# pro2310.net
KiCad netlist of a schematic drawn in EAGLE
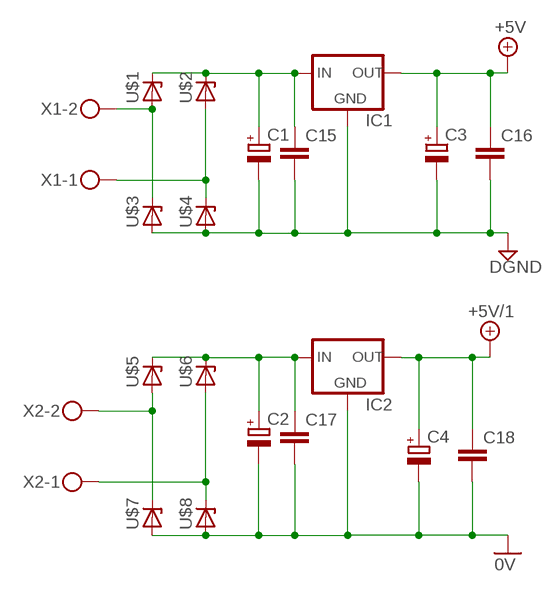
[diagram p0: schematic, sheet 1]
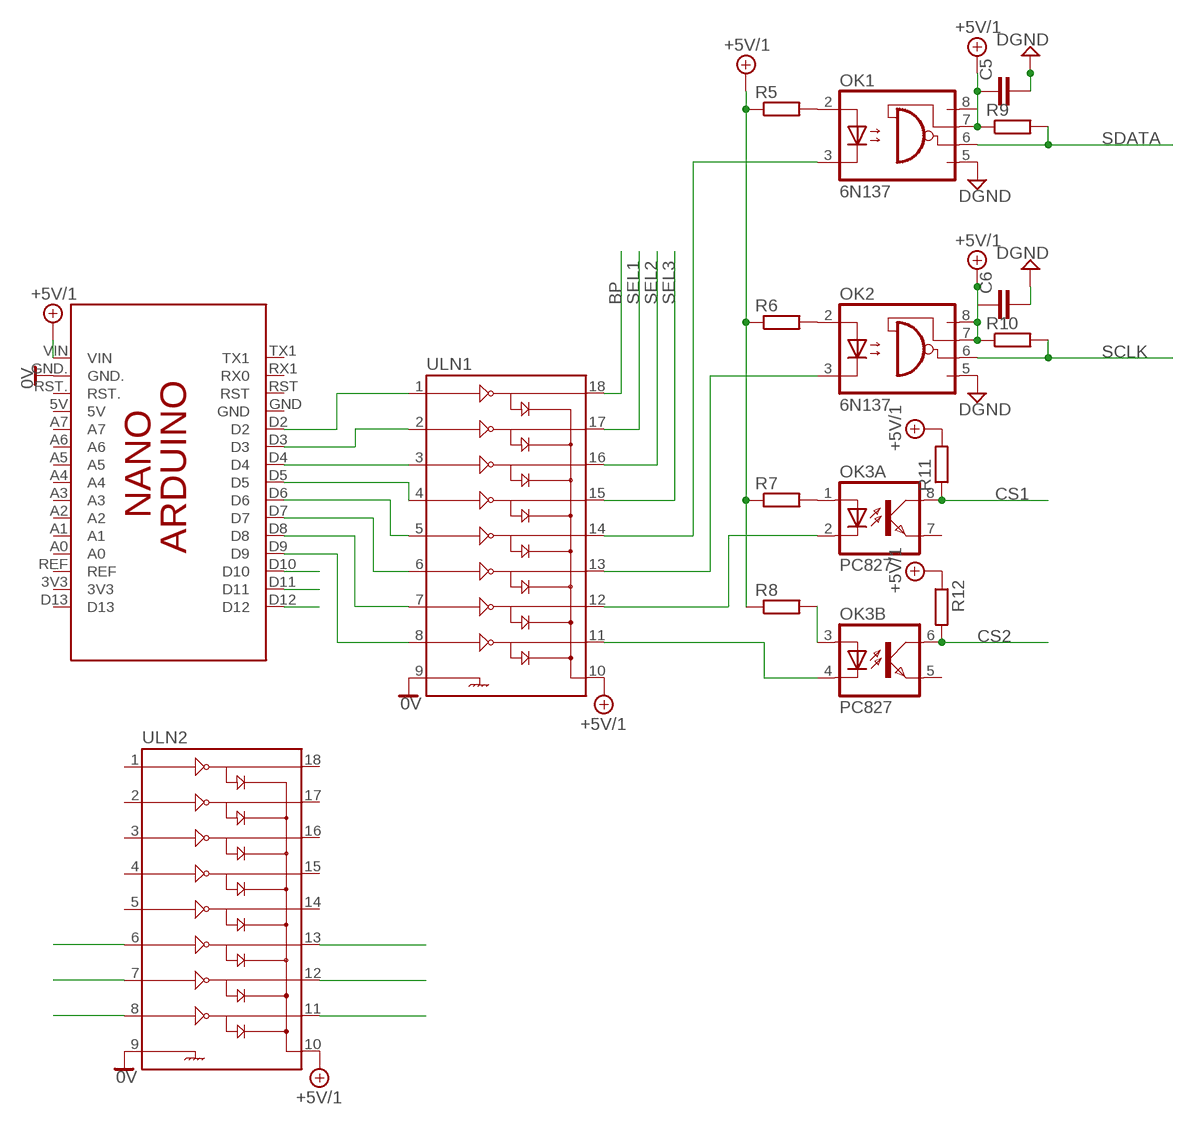
[diagram p1: schematic, sheet 2]
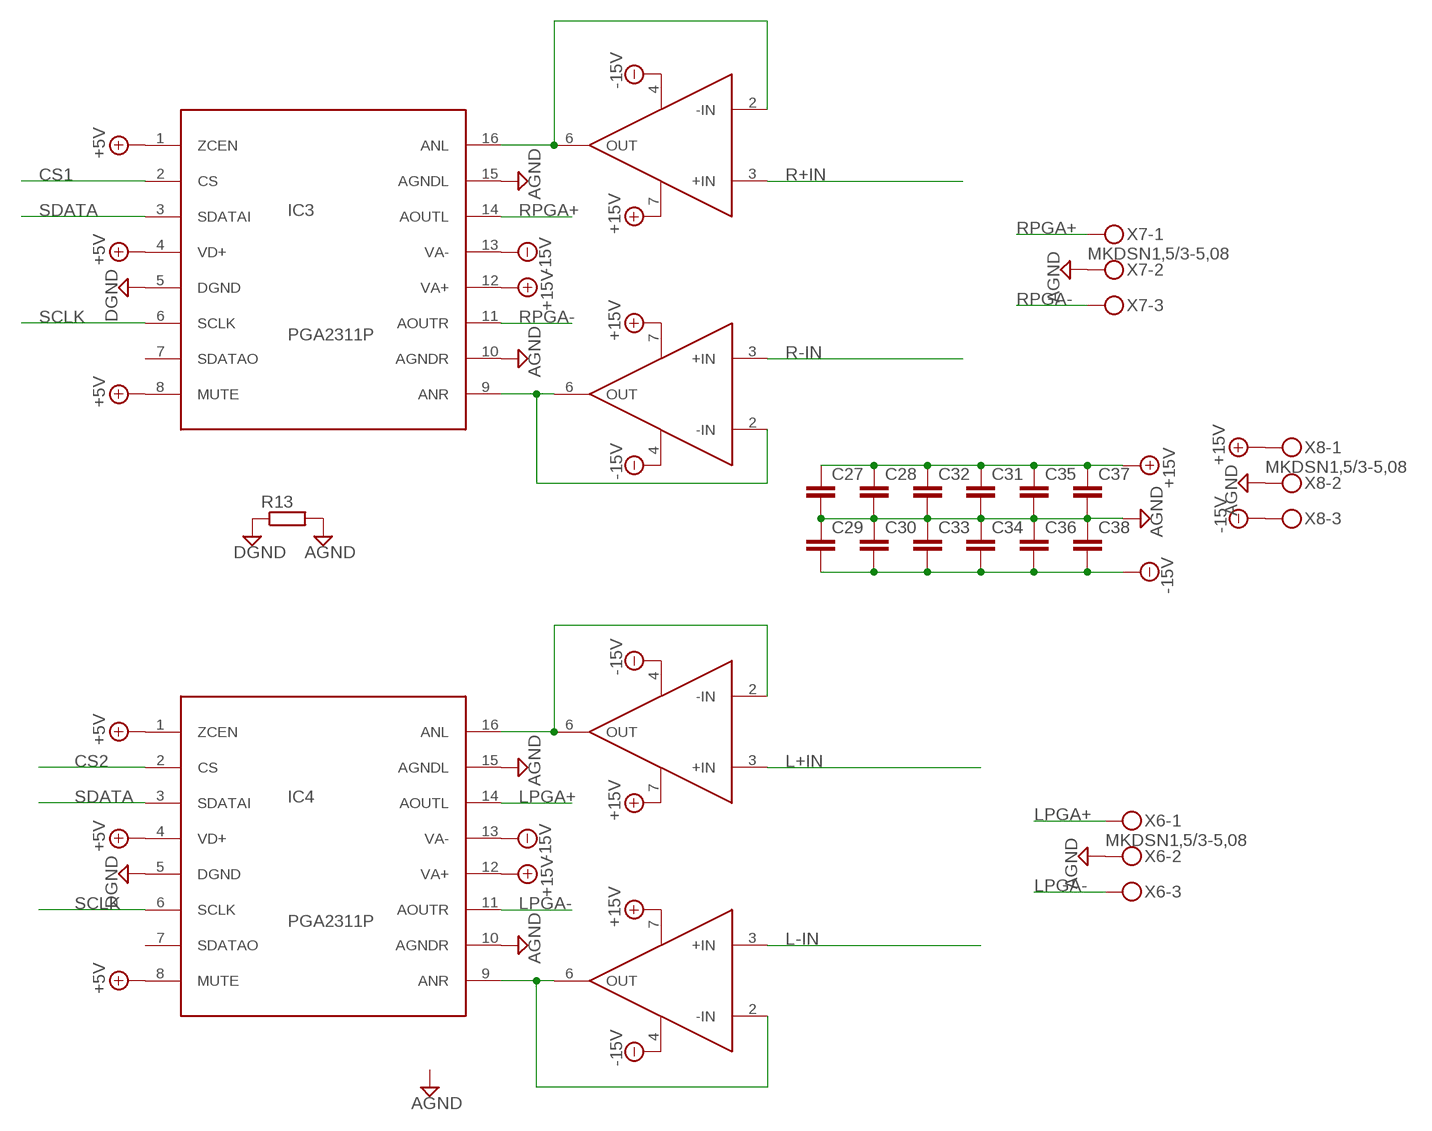
[diagram p2: schematic, sheet 3]
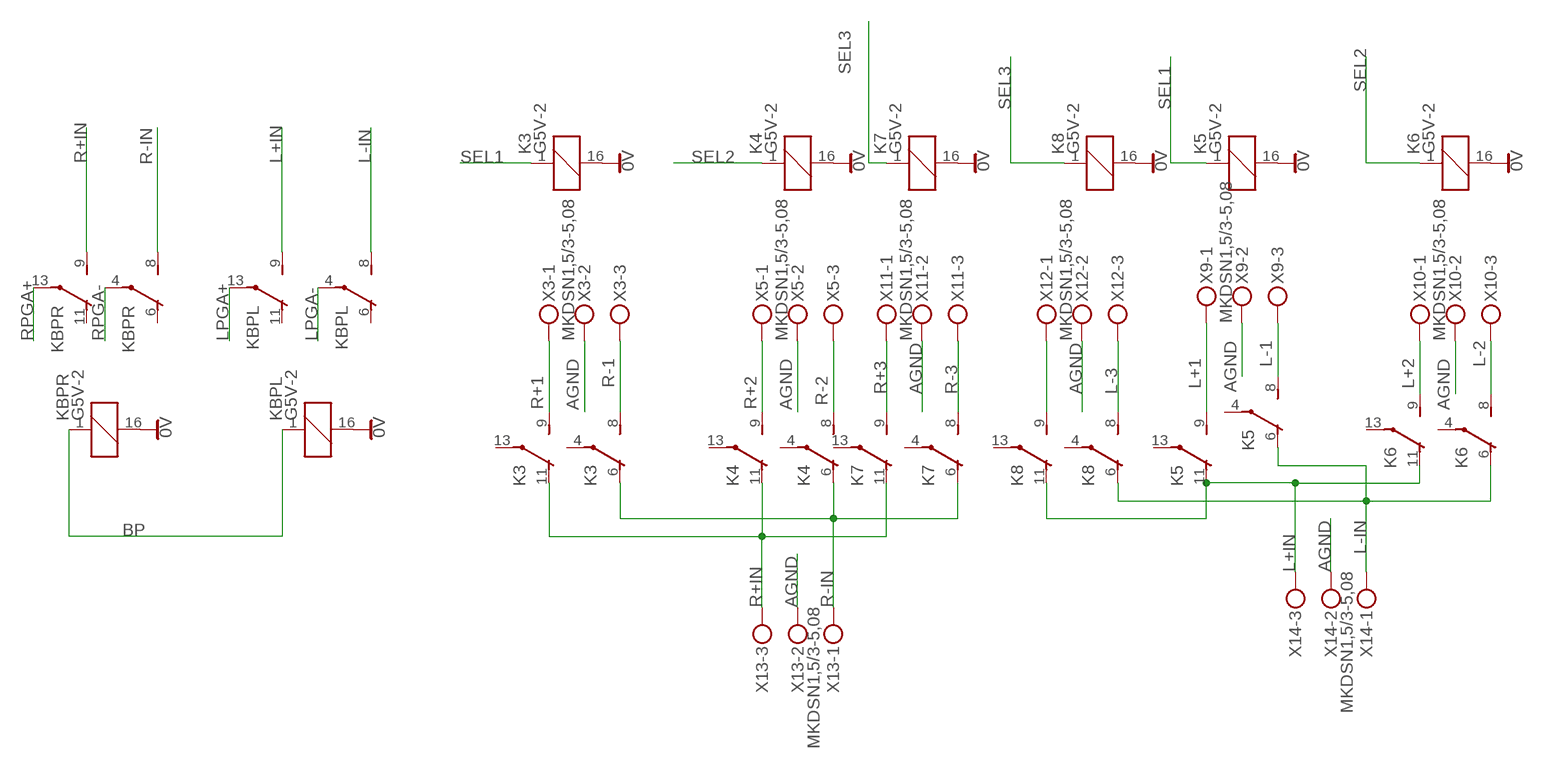
[diagram p3: schematic, sheet 4]
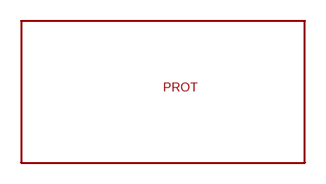
[diagram p4: schematic, sheet 5]
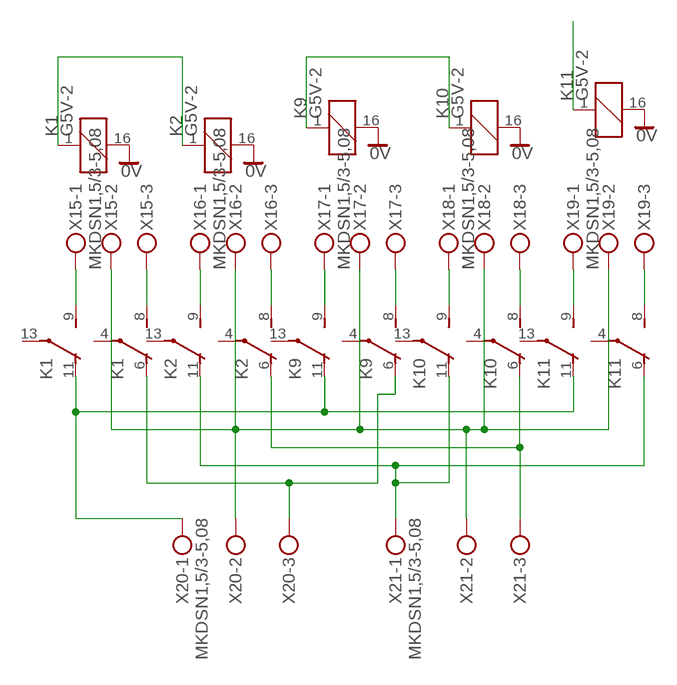
[diagram p5: schematic, sheet 6]

(export (version "E")
  (design (tool "Eeschema 10.0.6"))
  (components
    (comp (ref "C5")
      (value "C-EU025-025X050")
      (footprint "eagle-import:C025-025X050")
      (libsource (lib "eagle-import") (part "C-EU025-025X050"))
    )
    (comp (ref "C6")
      (value "C-EU025-025X050")
      (footprint "eagle-import:C025-025X050")
      (libsource (lib "eagle-import") (part "C-EU025-025X050"))
    )
    (comp (ref "OK1")
      (value "6N137")
      (footprint "eagle-import:DIL08")
      (libsource (lib "eagle-import") (part "6N137"))
    )
    (comp (ref "OK2")
      (value "6N137")
      (footprint "eagle-import:DIL08")
      (libsource (lib "eagle-import") (part "6N137"))
    )
    (comp (ref "OK3")
      (value "PC827")
      (footprint "eagle-import:DIL08")
      (libsource (lib "eagle-import") (part "PC827"))
    )
    (comp (ref "PCB1")
      (value "ARDUINO_NANO")
      (footprint "eagle-import:ARDUINO_NANO")
      (libsource (lib "eagle-import") (part "ARDUINO_NANO"))
    )
    (comp (ref "R5")
      (value "R-EU_0207/2V")
      (footprint "eagle-import:0207_2V")
      (libsource (lib "eagle-import") (part "R-EU_0207/2V"))
    )
    (comp (ref "R6")
      (value "R-EU_0207/2V")
      (footprint "eagle-import:0207_2V")
      (libsource (lib "eagle-import") (part "R-EU_0207/2V"))
    )
    (comp (ref "R7")
      (value "R-EU_0207/2V")
      (footprint "eagle-import:0207_2V")
      (libsource (lib "eagle-import") (part "R-EU_0207/2V"))
    )
    (comp (ref "R8")
      (value "R-EU_0207/2V")
      (footprint "eagle-import:0207_2V")
      (libsource (lib "eagle-import") (part "R-EU_0207/2V"))
    )
    (comp (ref "R9")
      (value "R-EU_0207/2V")
      (footprint "eagle-import:0207_2V")
      (libsource (lib "eagle-import") (part "R-EU_0207/2V"))
    )
    (comp (ref "R10")
      (value "R-EU_0207/2V")
      (footprint "eagle-import:0207_2V")
      (libsource (lib "eagle-import") (part "R-EU_0207/2V"))
    )
    (comp (ref "R11")
      (value "R-EU_0207/2V")
      (footprint "eagle-import:0207_2V")
      (libsource (lib "eagle-import") (part "R-EU_0207/2V"))
    )
    (comp (ref "R12")
      (value "R-EU_0207/2V")
      (footprint "eagle-import:0207_2V")
      (libsource (lib "eagle-import") (part "R-EU_0207/2V"))
    )
    (comp (ref "ULN1")
      (value "ULN2803DIP")
      (footprint "eagle-import:DIL18")
      (libsource (lib "eagle-import") (part "ULN2803DIP"))
    )
    (comp (ref "ULN2")
      (value "ULN2803DIP")
      (footprint "eagle-import:DIL18")
      (libsource (lib "eagle-import") (part "ULN2803DIP"))
    )
    (comp (ref "U$15")
      (value "PROT")
      (footprint "eagle-import:PROT")
      (libsource (lib "eagle-import") (part "PROT"))
    )
    (comp (ref "K1")
      (value "G5V-2")
      (footprint "eagle-import:G5V-2")
      (fields (field (name "MPN") "G5V-2 5DC"))
      (libsource (lib "eagle-import") (part "G5V-2"))
    )
    (comp (ref "K2")
      (value "G5V-2")
      (footprint "eagle-import:G5V-2")
      (fields (field (name "MPN") "G5V-2 5DC"))
      (libsource (lib "eagle-import") (part "G5V-2"))
    )
    (comp (ref "K9")
      (value "G5V-2")
      (footprint "eagle-import:G5V-2")
      (fields (field (name "MPN") "G5V-2 5DC"))
      (libsource (lib "eagle-import") (part "G5V-2"))
    )
    (comp (ref "K10")
      (value "G5V-2")
      (footprint "eagle-import:G5V-2")
      (fields (field (name "MPN") "G5V-2 5DC"))
      (libsource (lib "eagle-import") (part "G5V-2"))
    )
    (comp (ref "K11")
      (value "G5V-2")
      (footprint "eagle-import:G5V-2")
      (fields (field (name "MPN") "G5V-2 5DC"))
      (libsource (lib "eagle-import") (part "G5V-2"))
    )
    (comp (ref "X15")
      (value "MKDSN1,5/3-5,08")
      (footprint "eagle-import:MKDSN1,5_3-5,08")
      (libsource (lib "eagle-import") (part "MKDSN1,5/3-5,08"))
    )
    (comp (ref "X16")
      (value "MKDSN1,5/3-5,08")
      (footprint "eagle-import:MKDSN1,5_3-5,08")
      (libsource (lib "eagle-import") (part "MKDSN1,5/3-5,08"))
    )
    (comp (ref "X17")
      (value "MKDSN1,5/3-5,08")
      (footprint "eagle-import:MKDSN1,5_3-5,08")
      (libsource (lib "eagle-import") (part "MKDSN1,5/3-5,08"))
    )
    (comp (ref "X18")
      (value "MKDSN1,5/3-5,08")
      (footprint "eagle-import:MKDSN1,5_3-5,08")
      (libsource (lib "eagle-import") (part "MKDSN1,5/3-5,08"))
    )
    (comp (ref "X19")
      (value "MKDSN1,5/3-5,08")
      (footprint "eagle-import:MKDSN1,5_3-5,08")
      (libsource (lib "eagle-import") (part "MKDSN1,5/3-5,08"))
    )
    (comp (ref "X20")
      (value "MKDSN1,5/3-5,08")
      (footprint "eagle-import:MKDSN1,5_3-5,08")
      (libsource (lib "eagle-import") (part "MKDSN1,5/3-5,08"))
    )
    (comp (ref "X21")
      (value "MKDSN1,5/3-5,08")
      (footprint "eagle-import:MKDSN1,5_3-5,08")
      (libsource (lib "eagle-import") (part "MKDSN1,5/3-5,08"))
    )
    (comp (ref "C27")
      (value "C-EU025-025X050")
      (footprint "eagle-import:C025-025X050")
      (libsource (lib "eagle-import") (part "C-EU025-025X050"))
    )
    (comp (ref "C28")
      (value "C-EU025-025X050")
      (footprint "eagle-import:C025-025X050")
      (libsource (lib "eagle-import") (part "C-EU025-025X050"))
    )
    (comp (ref "C29")
      (value "C-EU025-025X050")
      (footprint "eagle-import:C025-025X050")
      (libsource (lib "eagle-import") (part "C-EU025-025X050"))
    )
    (comp (ref "C30")
      (value "C-EU025-025X050")
      (footprint "eagle-import:C025-025X050")
      (libsource (lib "eagle-import") (part "C-EU025-025X050"))
    )
    (comp (ref "C31")
      (value "C-EU025-025X050")
      (footprint "eagle-import:C025-025X050")
      (libsource (lib "eagle-import") (part "C-EU025-025X050"))
    )
    (comp (ref "C32")
      (value "C-EU025-025X050")
      (footprint "eagle-import:C025-025X050")
      (libsource (lib "eagle-import") (part "C-EU025-025X050"))
    )
    (comp (ref "C33")
      (value "C-EU025-025X050")
      (footprint "eagle-import:C025-025X050")
      (libsource (lib "eagle-import") (part "C-EU025-025X050"))
    )
    (comp (ref "C34")
      (value "C-EU025-025X050")
      (footprint "eagle-import:C025-025X050")
      (libsource (lib "eagle-import") (part "C-EU025-025X050"))
    )
    (comp (ref "C35")
      (value "C-EU025-025X050")
      (footprint "eagle-import:C025-025X050")
      (libsource (lib "eagle-import") (part "C-EU025-025X050"))
    )
    (comp (ref "C36")
      (value "C-EU025-025X050")
      (footprint "eagle-import:C025-025X050")
      (libsource (lib "eagle-import") (part "C-EU025-025X050"))
    )
    (comp (ref "C37")
      (value "C-EU025-025X050")
      (footprint "eagle-import:C025-025X050")
      (libsource (lib "eagle-import") (part "C-EU025-025X050"))
    )
    (comp (ref "C38")
      (value "C-EU025-025X050")
      (footprint "eagle-import:C025-025X050")
      (libsource (lib "eagle-import") (part "C-EU025-025X050"))
    )
    (comp (ref "IC3")
      (value "PGA2311P")
      (footprint "eagle-import:DIL16")
      (libsource (lib "eagle-import") (part "PGA2311P"))
    )
    (comp (ref "IC4")
      (value "PGA2311P")
      (footprint "eagle-import:DIL16")
      (libsource (lib "eagle-import") (part "PGA2311P"))
    )
    (comp (ref "R13")
      (value "R-EU_0207/7")
      (footprint "eagle-import:0207_7")
      (libsource (lib "eagle-import") (part "R-EU_0207/7"))
    )
    (comp (ref "U1")
      (value "OPA627BP")
      (footprint "eagle-import:DIL08")
      (libsource (lib "eagle-import") (part "OPA627BP"))
    )
    (comp (ref "U2")
      (value "OPA627BP")
      (footprint "eagle-import:DIL08")
      (libsource (lib "eagle-import") (part "OPA627BP"))
    )
    (comp (ref "U3")
      (value "OPA627BP")
      (footprint "eagle-import:DIL08")
      (libsource (lib "eagle-import") (part "OPA627BP"))
    )
    (comp (ref "U4")
      (value "OPA627BP")
      (footprint "eagle-import:DIL08")
      (libsource (lib "eagle-import") (part "OPA627BP"))
    )
    (comp (ref "X6")
      (value "MKDSN1,5/3-5,08")
      (footprint "eagle-import:MKDSN1,5_3-5,08")
      (libsource (lib "eagle-import") (part "MKDSN1,5/3-5,08"))
    )
    (comp (ref "X7")
      (value "MKDSN1,5/3-5,08")
      (footprint "eagle-import:MKDSN1,5_3-5,08")
      (libsource (lib "eagle-import") (part "MKDSN1,5/3-5,08"))
    )
    (comp (ref "X8")
      (value "MKDSN1,5/3-5,08")
      (footprint "eagle-import:MKDSN1,5_3-5,08")
      (libsource (lib "eagle-import") (part "MKDSN1,5/3-5,08"))
    )
    (comp (ref "C1")
      (value "CPOL-EUE5-10.5")
      (footprint "eagle-import:E5-10,5")
      (libsource (lib "eagle-import") (part "CPOL-EUE5-10.5"))
    )
    (comp (ref "C2")
      (value "CPOL-EUE5-10.5")
      (footprint "eagle-import:E5-10,5")
      (libsource (lib "eagle-import") (part "CPOL-EUE5-10.5"))
    )
    (comp (ref "C3")
      (value "CPOL-EUE3.5-8")
      (footprint "eagle-import:E3,5-8")
      (libsource (lib "eagle-import") (part "CPOL-EUE3.5-8"))
    )
    (comp (ref "C4")
      (value "CPOL-EUE3.5-8")
      (footprint "eagle-import:E3,5-8")
      (libsource (lib "eagle-import") (part "CPOL-EUE3.5-8"))
    )
    (comp (ref "C15")
      (value "C-EU050-055X075")
      (footprint "eagle-import:C050-055X075")
      (libsource (lib "eagle-import") (part "C-EU050-055X075"))
    )
    (comp (ref "C16")
      (value "C-EU050-055X075")
      (footprint "eagle-import:C050-055X075")
      (libsource (lib "eagle-import") (part "C-EU050-055X075"))
    )
    (comp (ref "C17")
      (value "C-EU050-055X075")
      (footprint "eagle-import:C050-055X075")
      (libsource (lib "eagle-import") (part "C-EU050-055X075"))
    )
    (comp (ref "C18")
      (value "C-EU050-055X075")
      (footprint "eagle-import:C050-055X075")
      (libsource (lib "eagle-import") (part "C-EU050-055X075"))
    )
    (comp (ref "IC1")
      (value "78LXX")
      (footprint "eagle-import:78LXX")
      (libsource (lib "eagle-import") (part "78LXX"))
    )
    (comp (ref "IC2")
      (value "78MXXL")
      (footprint "eagle-import:78MXXL")
      (libsource (lib "eagle-import") (part "78MXXL"))
    )
    (comp (ref "U$1")
      (value "1N4148-V")
      (footprint "eagle-import:1N4148")
      (libsource (lib "eagle-import") (part "1N4148-V"))
    )
    (comp (ref "U$2")
      (value "1N4148-V")
      (footprint "eagle-import:1N4148")
      (libsource (lib "eagle-import") (part "1N4148-V"))
    )
    (comp (ref "U$3")
      (value "1N4148-V")
      (footprint "eagle-import:1N4148")
      (libsource (lib "eagle-import") (part "1N4148-V"))
    )
    (comp (ref "U$4")
      (value "1N4148-V")
      (footprint "eagle-import:1N4148")
      (libsource (lib "eagle-import") (part "1N4148-V"))
    )
    (comp (ref "U$5")
      (value "1N4148-V")
      (footprint "eagle-import:1N4148")
      (libsource (lib "eagle-import") (part "1N4148-V"))
    )
    (comp (ref "U$6")
      (value "1N4148-V")
      (footprint "eagle-import:1N4148")
      (libsource (lib "eagle-import") (part "1N4148-V"))
    )
    (comp (ref "U$7")
      (value "1N4148-V")
      (footprint "eagle-import:1N4148")
      (libsource (lib "eagle-import") (part "1N4148-V"))
    )
    (comp (ref "U$8")
      (value "1N4148-V")
      (footprint "eagle-import:1N4148")
      (libsource (lib "eagle-import") (part "1N4148-V"))
    )
    (comp (ref "X1")
      (value "MKDSN1,5/2-5,08")
      (footprint "eagle-import:MKDSN1,5_2-5,08")
      (libsource (lib "eagle-import") (part "MKDSN1,5/2-5,08"))
    )
    (comp (ref "X2")
      (value "MKDSN1,5/2-5,08")
      (footprint "eagle-import:MKDSN1,5_2-5,08")
      (libsource (lib "eagle-import") (part "MKDSN1,5/2-5,08"))
    )
    (comp (ref "K3")
      (value "G5V-2")
      (footprint "eagle-import:G5V-2")
      (fields (field (name "MPN") "G5V-2 5DC"))
      (libsource (lib "eagle-import") (part "G5V-2"))
    )
    (comp (ref "K4")
      (value "G5V-2")
      (footprint "eagle-import:G5V-2")
      (fields (field (name "MPN") "G5V-2 5DC"))
      (libsource (lib "eagle-import") (part "G5V-2"))
    )
    (comp (ref "K5")
      (value "G5V-2")
      (footprint "eagle-import:G5V-2")
      (fields (field (name "MPN") "G5V-2 5DC"))
      (libsource (lib "eagle-import") (part "G5V-2"))
    )
    (comp (ref "K6")
      (value "G5V-2")
      (footprint "eagle-import:G5V-2")
      (fields (field (name "MPN") "G5V-2 5DC"))
      (libsource (lib "eagle-import") (part "G5V-2"))
    )
    (comp (ref "K7")
      (value "G5V-2")
      (footprint "eagle-import:G5V-2")
      (fields (field (name "MPN") "G5V-2 5DC"))
      (libsource (lib "eagle-import") (part "G5V-2"))
    )
    (comp (ref "K8")
      (value "G5V-2")
      (footprint "eagle-import:G5V-2")
      (fields (field (name "MPN") "G5V-2 5DC"))
      (libsource (lib "eagle-import") (part "G5V-2"))
    )
    (comp (ref "KBPL")
      (value "G5V-2")
      (footprint "eagle-import:G5V-2")
      (fields (field (name "MPN") "G5V-2 5DC"))
      (libsource (lib "eagle-import") (part "G5V-2"))
    )
    (comp (ref "KBPR")
      (value "G5V-2")
      (footprint "eagle-import:G5V-2")
      (fields (field (name "MPN") "G5V-2 5DC"))
      (libsource (lib "eagle-import") (part "G5V-2"))
    )
    (comp (ref "X3")
      (value "MKDSN1,5/3-5,08")
      (footprint "eagle-import:MKDSN1,5_3-5,08")
      (libsource (lib "eagle-import") (part "MKDSN1,5/3-5,08"))
    )
    (comp (ref "X5")
      (value "MKDSN1,5/3-5,08")
      (footprint "eagle-import:MKDSN1,5_3-5,08")
      (libsource (lib "eagle-import") (part "MKDSN1,5/3-5,08"))
    )
    (comp (ref "X9")
      (value "MKDSN1,5/3-5,08")
      (footprint "eagle-import:MKDSN1,5_3-5,08")
      (libsource (lib "eagle-import") (part "MKDSN1,5/3-5,08"))
    )
    (comp (ref "X10")
      (value "MKDSN1,5/3-5,08")
      (footprint "eagle-import:MKDSN1,5_3-5,08")
      (libsource (lib "eagle-import") (part "MKDSN1,5/3-5,08"))
    )
    (comp (ref "X11")
      (value "MKDSN1,5/3-5,08")
      (footprint "eagle-import:MKDSN1,5_3-5,08")
      (libsource (lib "eagle-import") (part "MKDSN1,5/3-5,08"))
    )
    (comp (ref "X12")
      (value "MKDSN1,5/3-5,08")
      (footprint "eagle-import:MKDSN1,5_3-5,08")
      (libsource (lib "eagle-import") (part "MKDSN1,5/3-5,08"))
    )
    (comp (ref "X13")
      (value "MKDSN1,5/3-5,08")
      (footprint "eagle-import:MKDSN1,5_3-5,08")
      (libsource (lib "eagle-import") (part "MKDSN1,5/3-5,08"))
    )
    (comp (ref "X14")
      (value "MKDSN1,5/3-5,08")
      (footprint "eagle-import:MKDSN1,5_3-5,08")
      (libsource (lib "eagle-import") (part "MKDSN1,5/3-5,08"))
    )
  )
  (nets
    (net (code "1") (name "+5V") (class "Default")
      (node (ref "C16") (pin "1") (pinfunction "1_1") (pintype "passive"))
      (node (ref "C3") (pin "+") (pinfunction "+_+") (pintype "passive"))
      (node (ref "IC1") (pin "OUT") (pinfunction "OUT_OUT") (pintype "passive"))
      (node (ref "IC3") (pin "1") (pinfunction "ZCEN_1") (pintype "input"))
      (node (ref "IC3") (pin "4") (pinfunction "VD+_4") (pintype "power_in"))
      (node (ref "IC3") (pin "8") (pinfunction "MUTE_8") (pintype "input"))
      (node (ref "IC4") (pin "1") (pinfunction "ZCEN_1") (pintype "input"))
      (node (ref "IC4") (pin "4") (pinfunction "VD+_4") (pintype "power_in"))
      (node (ref "IC4") (pin "8") (pinfunction "MUTE_8") (pintype "input"))
    )
    (net (code "2") (name "+5V{slash}1") (class "Default")
      (node (ref "C18") (pin "1") (pinfunction "1_1") (pintype "passive"))
      (node (ref "C4") (pin "+") (pinfunction "+_+") (pintype "passive"))
      (node (ref "C5") (pin "1") (pinfunction "1_1") (pintype "passive"))
      (node (ref "C6") (pin "1") (pinfunction "1_1") (pintype "passive"))
      (node (ref "IC2") (pin "OUT") (pinfunction "OUT_OUT") (pintype "passive"))
      (node (ref "OK1") (pin "7") (pinfunction "VE_7") (pintype "passive"))
      (node (ref "OK1") (pin "8") (pinfunction "VCC_8") (pintype "passive"))
      (node (ref "OK2") (pin "7") (pinfunction "VE_7") (pintype "passive"))
      (node (ref "OK2") (pin "8") (pinfunction "VCC_8") (pintype "passive"))
      (node (ref "PCB1") (pin "VIN") (pinfunction "VIN_VIN") (pintype "bidirectional"))
      (node (ref "R10") (pin "1") (pinfunction "1_1") (pintype "passive"))
      (node (ref "R11") (pin "2") (pinfunction "2_2") (pintype "passive"))
      (node (ref "R12") (pin "1") (pinfunction "1_1") (pintype "passive"))
      (node (ref "R5") (pin "1") (pinfunction "1_1") (pintype "passive"))
      (node (ref "R6") (pin "1") (pinfunction "1_1") (pintype "passive"))
      (node (ref "R7") (pin "1") (pinfunction "1_1") (pintype "passive"))
      (node (ref "R8") (pin "1") (pinfunction "1_1") (pintype "passive"))
      (node (ref "R9") (pin "1") (pinfunction "1_1") (pintype "passive"))
      (node (ref "ULN1") (pin "10") (pinfunction "10_10") (pintype "bidirectional"))
      (node (ref "ULN2") (pin "10") (pinfunction "10_10") (pintype "bidirectional"))
    )
    (net (code "3") (name "+15V") (class "Default")
      (node (ref "C27") (pin "1") (pinfunction "1_1") (pintype "passive"))
      (node (ref "C28") (pin "1") (pinfunction "1_1") (pintype "passive"))
      (node (ref "C31") (pin "1") (pinfunction "1_1") (pintype "passive"))
      (node (ref "C32") (pin "1") (pinfunction "1_1") (pintype "passive"))
      (node (ref "C35") (pin "1") (pinfunction "1_1") (pintype "passive"))
      (node (ref "C37") (pin "1") (pinfunction "1_1") (pintype "passive"))
      (node (ref "IC3") (pin "12") (pinfunction "VA+_12") (pintype "power_in"))
      (node (ref "IC4") (pin "12") (pinfunction "VA+_12") (pintype "power_in"))
      (node (ref "U1") (pin "7") (pinfunction "V+_7") (pintype "bidirectional"))
      (node (ref "U2") (pin "7") (pinfunction "V+_7") (pintype "bidirectional"))
      (node (ref "U3") (pin "7") (pinfunction "V+_7") (pintype "bidirectional"))
      (node (ref "U4") (pin "7") (pinfunction "V+_7") (pintype "bidirectional"))
      (node (ref "X8") (pin "1") (pinfunction "KL_1") (pintype "passive"))
    )
    (net (code "4") (name "-15V") (class "Default")
      (node (ref "C29") (pin "2") (pinfunction "2_2") (pintype "passive"))
      (node (ref "C30") (pin "2") (pinfunction "2_2") (pintype "passive"))
      (node (ref "C33") (pin "2") (pinfunction "2_2") (pintype "passive"))
      (node (ref "C34") (pin "2") (pinfunction "2_2") (pintype "passive"))
      (node (ref "C36") (pin "2") (pinfunction "2_2") (pintype "passive"))
      (node (ref "C38") (pin "2") (pinfunction "2_2") (pintype "passive"))
      (node (ref "IC3") (pin "13") (pinfunction "VA-_13") (pintype "power_in"))
      (node (ref "IC4") (pin "13") (pinfunction "VA-_13") (pintype "power_in"))
      (node (ref "U1") (pin "4") (pinfunction "V-_4") (pintype "bidirectional"))
      (node (ref "U2") (pin "4") (pinfunction "V-_4") (pintype "bidirectional"))
      (node (ref "U3") (pin "4") (pinfunction "V-_4") (pintype "bidirectional"))
      (node (ref "U4") (pin "4") (pinfunction "V-_4") (pintype "bidirectional"))
      (node (ref "X8") (pin "3") (pinfunction "KL_3") (pintype "passive"))
    )
    (net (code "5") (name "0V") (class "Default")
      (node (ref "C17") (pin "2") (pinfunction "2_2") (pintype "passive"))
      (node (ref "C18") (pin "2") (pinfunction "2_2") (pintype "passive"))
      (node (ref "C2") (pin "-") (pinfunction "-_-") (pintype "passive"))
      (node (ref "C4") (pin "-") (pinfunction "-_-") (pintype "passive"))
      (node (ref "IC2") (pin "GND") (pinfunction "GND_GND") (pintype "input"))
      (node (ref "K1") (pin "16") (pinfunction "2_16") (pintype "passive"))
      (node (ref "K10") (pin "16") (pinfunction "2_16") (pintype "passive"))
      (node (ref "K11") (pin "16") (pinfunction "2_16") (pintype "passive"))
      (node (ref "K2") (pin "16") (pinfunction "2_16") (pintype "passive"))
      (node (ref "K3") (pin "16") (pinfunction "2_16") (pintype "passive"))
      (node (ref "K4") (pin "16") (pinfunction "2_16") (pintype "passive"))
      (node (ref "K5") (pin "16") (pinfunction "2_16") (pintype "passive"))
      (node (ref "K6") (pin "16") (pinfunction "2_16") (pintype "passive"))
      (node (ref "K7") (pin "16") (pinfunction "2_16") (pintype "passive"))
      (node (ref "K8") (pin "16") (pinfunction "2_16") (pintype "passive"))
      (node (ref "K9") (pin "16") (pinfunction "2_16") (pintype "passive"))
      (node (ref "KBPL") (pin "16") (pinfunction "2_16") (pintype "passive"))
      (node (ref "KBPR") (pin "16") (pinfunction "2_16") (pintype "passive"))
      (node (ref "PCB1") (pin "GND.") (pinfunction "GND._GND.") (pintype "bidirectional"))
      (node (ref "U$7") (pin "A") (pinfunction "A_A") (pintype "passive"))
      (node (ref "U$8") (pin "A") (pinfunction "A_A") (pintype "passive"))
      (node (ref "ULN1") (pin "9") (pinfunction "9_9") (pintype "bidirectional"))
      (node (ref "ULN2") (pin "9") (pinfunction "9_9") (pintype "bidirectional"))
    )
    (net (code "6") (name "AGND") (class "Default")
      (node (ref "C27") (pin "2") (pinfunction "2_2") (pintype "passive"))
      (node (ref "C28") (pin "2") (pinfunction "2_2") (pintype "passive"))
      (node (ref "C29") (pin "1") (pinfunction "1_1") (pintype "passive"))
      (node (ref "C30") (pin "1") (pinfunction "1_1") (pintype "passive"))
      (node (ref "C31") (pin "2") (pinfunction "2_2") (pintype "passive"))
      (node (ref "C32") (pin "2") (pinfunction "2_2") (pintype "passive"))
      (node (ref "C33") (pin "1") (pinfunction "1_1") (pintype "passive"))
      (node (ref "C34") (pin "1") (pinfunction "1_1") (pintype "passive"))
      (node (ref "C35") (pin "2") (pinfunction "2_2") (pintype "passive"))
      (node (ref "C36") (pin "1") (pinfunction "1_1") (pintype "passive"))
      (node (ref "C37") (pin "2") (pinfunction "2_2") (pintype "passive"))
      (node (ref "C38") (pin "1") (pinfunction "1_1") (pintype "passive"))
      (node (ref "IC3") (pin "10") (pinfunction "AGNDR_10") (pintype "power_in"))
      (node (ref "IC3") (pin "15") (pinfunction "AGNDL_15") (pintype "power_in"))
      (node (ref "IC4") (pin "10") (pinfunction "AGNDR_10") (pintype "power_in"))
      (node (ref "IC4") (pin "15") (pinfunction "AGNDL_15") (pintype "power_in"))
      (node (ref "R13") (pin "2") (pinfunction "2_2") (pintype "passive"))
      (node (ref "X10") (pin "2") (pinfunction "KL_2") (pintype "passive"))
      (node (ref "X11") (pin "2") (pinfunction "KL_2") (pintype "passive"))
      (node (ref "X12") (pin "2") (pinfunction "KL_2") (pintype "passive"))
      (node (ref "X13") (pin "2") (pinfunction "KL_2") (pintype "passive"))
      (node (ref "X14") (pin "2") (pinfunction "KL_2") (pintype "passive"))
      (node (ref "X3") (pin "2") (pinfunction "KL_2") (pintype "passive"))
      (node (ref "X5") (pin "2") (pinfunction "KL_2") (pintype "passive"))
      (node (ref "X6") (pin "2") (pinfunction "KL_2") (pintype "passive"))
      (node (ref "X7") (pin "2") (pinfunction "KL_2") (pintype "passive"))
      (node (ref "X8") (pin "2") (pinfunction "KL_2") (pintype "passive"))
      (node (ref "X9") (pin "2") (pinfunction "KL_2") (pintype "passive"))
    )
    (net (code "7") (name "BP") (class "Default")
      (node (ref "KBPL") (pin "1") (pinfunction "1_1") (pintype "passive"))
      (node (ref "KBPR") (pin "1") (pinfunction "1_1") (pintype "passive"))
      (node (ref "ULN1") (pin "18") (pinfunction "18_18") (pintype "bidirectional"))
    )
    (net (code "8") (name "CS1") (class "Default")
      (node (ref "IC3") (pin "2") (pinfunction "CS_2") (pintype "bidirectional"))
      (node (ref "OK3") (pin "8") (pinfunction "COL_8") (pintype "passive"))
      (node (ref "R11") (pin "1") (pinfunction "1_1") (pintype "passive"))
    )
    (net (code "9") (name "CS2") (class "Default")
      (node (ref "IC4") (pin "2") (pinfunction "CS_2") (pintype "bidirectional"))
      (node (ref "OK3") (pin "6") (pinfunction "COL_6") (pintype "passive"))
      (node (ref "R12") (pin "2") (pinfunction "2_2") (pintype "passive"))
    )
    (net (code "10") (name "D10") (class "Default")
      (node (ref "PCB1") (pin "D10") (pinfunction "D10_D10") (pintype "bidirectional"))
      (node (ref "ULN2") (pin "8") (pinfunction "8_8") (pintype "bidirectional"))
    )
    (net (code "11") (name "D11") (class "Default")
      (node (ref "PCB1") (pin "D11") (pinfunction "D11_D11") (pintype "bidirectional"))
      (node (ref "ULN2") (pin "7") (pinfunction "7_7") (pintype "bidirectional"))
    )
    (net (code "12") (name "D12") (class "Default")
      (node (ref "PCB1") (pin "D12") (pinfunction "D12_D12") (pintype "bidirectional"))
      (node (ref "ULN2") (pin "6") (pinfunction "6_6") (pintype "bidirectional"))
    )
    (net (code "13") (name "DGND") (class "Default")
      (node (ref "C1") (pin "-") (pinfunction "-_-") (pintype "passive"))
      (node (ref "C15") (pin "2") (pinfunction "2_2") (pintype "passive"))
      (node (ref "C16") (pin "2") (pinfunction "2_2") (pintype "passive"))
      (node (ref "C3") (pin "-") (pinfunction "-_-") (pintype "passive"))
      (node (ref "C5") (pin "2") (pinfunction "2_2") (pintype "passive"))
      (node (ref "C6") (pin "2") (pinfunction "2_2") (pintype "passive"))
      (node (ref "IC1") (pin "GND") (pinfunction "GND_GND") (pintype "input"))
      (node (ref "IC3") (pin "5") (pinfunction "DGND_5") (pintype "power_in"))
      (node (ref "IC4") (pin "5") (pinfunction "DGND_5") (pintype "power_in"))
      (node (ref "OK1") (pin "5") (pinfunction "GND_5") (pintype "passive"))
      (node (ref "OK2") (pin "5") (pinfunction "GND_5") (pintype "passive"))
      (node (ref "R13") (pin "1") (pinfunction "1_1") (pintype "passive"))
      (node (ref "U$3") (pin "A") (pinfunction "A_A") (pintype "passive"))
      (node (ref "U$4") (pin "A") (pinfunction "A_A") (pintype "passive"))
    )
    (net (code "14") (name "L+1") (class "Default")
      (node (ref "K5") (pin "9") (pinfunction "S_9") (pintype "passive"))
      (node (ref "X9") (pin "1") (pinfunction "KL_1") (pintype "passive"))
    )
    (net (code "15") (name "L+2") (class "Default")
      (node (ref "K6") (pin "9") (pinfunction "S_9") (pintype "passive"))
      (node (ref "X10") (pin "1") (pinfunction "KL_1") (pintype "passive"))
    )
    (net (code "16") (name "L+IN") (class "Default")
      (node (ref "K5") (pin "11") (pinfunction "O_11") (pintype "passive"))
      (node (ref "K6") (pin "11") (pinfunction "O_11") (pintype "passive"))
      (node (ref "K8") (pin "11") (pinfunction "O_11") (pintype "passive"))
      (node (ref "KBPL") (pin "9") (pinfunction "S_9") (pintype "passive"))
      (node (ref "U3") (pin "3") (pinfunction "+IN_3") (pintype "bidirectional"))
      (node (ref "X14") (pin "3") (pinfunction "KL_3") (pintype "passive"))
    )
    (net (code "17") (name "L-1") (class "Default")
      (node (ref "K5") (pin "8") (pinfunction "S_8") (pintype "passive"))
      (node (ref "X9") (pin "3") (pinfunction "KL_3") (pintype "passive"))
    )
    (net (code "18") (name "L-2") (class "Default")
      (node (ref "K6") (pin "8") (pinfunction "S_8") (pintype "passive"))
      (node (ref "X10") (pin "3") (pinfunction "KL_3") (pintype "passive"))
    )
    (net (code "19") (name "L-3") (class "Default")
      (node (ref "K8") (pin "8") (pinfunction "S_8") (pintype "passive"))
      (node (ref "X12") (pin "3") (pinfunction "KL_3") (pintype "passive"))
    )
    (net (code "20") (name "L-IN") (class "Default")
      (node (ref "K5") (pin "6") (pinfunction "O_6") (pintype "passive"))
      (node (ref "K6") (pin "6") (pinfunction "O_6") (pintype "passive"))
      (node (ref "K8") (pin "6") (pinfunction "O_6") (pintype "passive"))
      (node (ref "KBPL") (pin "8") (pinfunction "S_8") (pintype "passive"))
      (node (ref "U4") (pin "3") (pinfunction "+IN_3") (pintype "bidirectional"))
      (node (ref "X14") (pin "1") (pinfunction "KL_1") (pintype "passive"))
    )
    (net (code "21") (name "LPGA+") (class "Default")
      (node (ref "IC4") (pin "14") (pinfunction "AOUTL_14") (pintype "output"))
      (node (ref "KBPL") (pin "13") (pinfunction "P_13") (pintype "passive"))
      (node (ref "X6") (pin "1") (pinfunction "KL_1") (pintype "passive"))
    )
    (net (code "22") (name "LPGA-") (class "Default")
      (node (ref "IC4") (pin "11") (pinfunction "AOUTR_11") (pintype "output"))
      (node (ref "KBPL") (pin "4") (pinfunction "P_4") (pintype "passive"))
      (node (ref "X6") (pin "3") (pinfunction "KL_3") (pintype "passive"))
    )
    (net (code "23") (name "Net-(C1-Pad+)") (class "Default")
      (node (ref "C1") (pin "+") (pinfunction "+_+") (pintype "passive"))
      (node (ref "C15") (pin "1") (pinfunction "1_1") (pintype "passive"))
      (node (ref "IC1") (pin "IN") (pinfunction "IN_IN") (pintype "input"))
      (node (ref "U$1") (pin "C") (pinfunction "C_C") (pintype "passive"))
      (node (ref "U$2") (pin "C") (pinfunction "C_C") (pintype "passive"))
    )
    (net (code "24") (name "Net-(C17-Pad1)") (class "Default")
      (node (ref "C17") (pin "1") (pinfunction "1_1") (pintype "passive"))
      (node (ref "C2") (pin "+") (pinfunction "+_+") (pintype "passive"))
      (node (ref "IC2") (pin "IN") (pinfunction "IN_IN") (pintype "input"))
      (node (ref "U$5") (pin "C") (pinfunction "C_C") (pintype "passive"))
      (node (ref "U$6") (pin "C") (pinfunction "C_C") (pintype "passive"))
    )
    (net (code "25") (name "Net-(IC3-ANL)") (class "Default")
      (node (ref "IC3") (pin "16") (pinfunction "ANL_16") (pintype "input"))
      (node (ref "U1") (pin "2") (pinfunction "-IN_2") (pintype "bidirectional"))
      (node (ref "U1") (pin "6") (pinfunction "OUT_6") (pintype "bidirectional"))
    )
    (net (code "26") (name "Net-(IC3-ANR)") (class "Default")
      (node (ref "IC3") (pin "9") (pinfunction "ANR_9") (pintype "input"))
      (node (ref "U2") (pin "2") (pinfunction "-IN_2") (pintype "bidirectional"))
      (node (ref "U2") (pin "6") (pinfunction "OUT_6") (pintype "bidirectional"))
    )
    (net (code "27") (name "Net-(IC4-ANL)") (class "Default")
      (node (ref "IC4") (pin "16") (pinfunction "ANL_16") (pintype "input"))
      (node (ref "U3") (pin "2") (pinfunction "-IN_2") (pintype "bidirectional"))
      (node (ref "U3") (pin "6") (pinfunction "OUT_6") (pintype "bidirectional"))
    )
    (net (code "28") (name "Net-(IC4-ANR)") (class "Default")
      (node (ref "IC4") (pin "9") (pinfunction "ANR_9") (pintype "input"))
      (node (ref "U4") (pin "2") (pinfunction "-IN_2") (pintype "bidirectional"))
      (node (ref "U4") (pin "6") (pinfunction "OUT_6") (pintype "bidirectional"))
    )
    (net (code "29") (name "Net-(K1A-O)") (class "Default")
      (node (ref "K1") (pin "6") (pinfunction "O_6") (pintype "passive"))
      (node (ref "K9") (pin "6") (pinfunction "O_6") (pintype "passive"))
      (node (ref "X20") (pin "3") (pinfunction "KL_3") (pintype "passive"))
    )
    (net (code "30") (name "Net-(K1A-S)") (class "Default")
      (node (ref "K1") (pin "8") (pinfunction "S_8") (pintype "passive"))
      (node (ref "X15") (pin "3") (pinfunction "KL_3") (pintype "passive"))
    )
    (net (code "31") (name "Net-(K1B-S)") (class "Default")
      (node (ref "K1") (pin "9") (pinfunction "S_9") (pintype "passive"))
      (node (ref "X15") (pin "1") (pinfunction "KL_1") (pintype "passive"))
    )
    (net (code "32") (name "Net-(K2A-S)") (class "Default")
      (node (ref "K2") (pin "8") (pinfunction "S_8") (pintype "passive"))
      (node (ref "X16") (pin "3") (pinfunction "KL_3") (pintype "passive"))
    )
    (net (code "33") (name "Net-(K2B-S)") (class "Default")
      (node (ref "K2") (pin "9") (pinfunction "S_9") (pintype "passive"))
      (node (ref "X16") (pin "1") (pinfunction "KL_1") (pintype "passive"))
    )
    (net (code "34") (name "Net-(K8B-S)") (class "Default")
      (node (ref "K8") (pin "9") (pinfunction "S_9") (pintype "passive"))
      (node (ref "X12") (pin "1") (pinfunction "KL_1") (pintype "passive"))
    )
    (net (code "35") (name "Net-(K9A-S)") (class "Default")
      (node (ref "K9") (pin "8") (pinfunction "S_8") (pintype "passive"))
      (node (ref "X17") (pin "3") (pinfunction "KL_3") (pintype "passive"))
    )
    (net (code "36") (name "Net-(K9B-S)") (class "Default")
      (node (ref "K9") (pin "9") (pinfunction "S_9") (pintype "passive"))
      (node (ref "X17") (pin "1") (pinfunction "KL_1") (pintype "passive"))
    )
    (net (code "37") (name "Net-(K10A-O)") (class "Default")
      (node (ref "K10") (pin "6") (pinfunction "O_6") (pintype "passive"))
      (node (ref "K2") (pin "6") (pinfunction "O_6") (pintype "passive"))
      (node (ref "X21") (pin "3") (pinfunction "KL_3") (pintype "passive"))
    )
    (net (code "38") (name "Net-(K10A-S)") (class "Default")
      (node (ref "K10") (pin "8") (pinfunction "S_8") (pintype "passive"))
      (node (ref "X18") (pin "3") (pinfunction "KL_3") (pintype "passive"))
    )
    (net (code "39") (name "Net-(K10B-O)") (class "Default")
      (node (ref "K10") (pin "11") (pinfunction "O_11") (pintype "passive"))
      (node (ref "K11") (pin "6") (pinfunction "O_6") (pintype "passive"))
      (node (ref "K2") (pin "11") (pinfunction "O_11") (pintype "passive"))
      (node (ref "X21") (pin "1") (pinfunction "KL_1") (pintype "passive"))
    )
    (net (code "40") (name "Net-(K10B-S)") (class "Default")
      (node (ref "K10") (pin "9") (pinfunction "S_9") (pintype "passive"))
      (node (ref "X18") (pin "1") (pinfunction "KL_1") (pintype "passive"))
    )
    (net (code "41") (name "Net-(K11A-S)") (class "Default")
      (node (ref "K11") (pin "8") (pinfunction "S_8") (pintype "passive"))
      (node (ref "X19") (pin "3") (pinfunction "KL_3") (pintype "passive"))
    )
    (net (code "42") (name "Net-(K11B-O)") (class "Default")
      (node (ref "K1") (pin "11") (pinfunction "O_11") (pintype "passive"))
      (node (ref "K11") (pin "11") (pinfunction "O_11") (pintype "passive"))
      (node (ref "K9") (pin "11") (pinfunction "O_11") (pintype "passive"))
      (node (ref "X20") (pin "1") (pinfunction "KL_1") (pintype "passive"))
    )
    (net (code "43") (name "Net-(K11B-S)") (class "Default")
      (node (ref "K11") (pin "9") (pinfunction "S_9") (pintype "passive"))
      (node (ref "X19") (pin "1") (pinfunction "KL_1") (pintype "passive"))
    )
    (net (code "44") (name "Net-(OK1-A)") (class "Default")
      (node (ref "OK1") (pin "2") (pinfunction "A_2") (pintype "passive"))
      (node (ref "R5") (pin "2") (pinfunction "2_2") (pintype "passive"))
    )
    (net (code "45") (name "Net-(OK1-C)") (class "Default")
      (node (ref "OK1") (pin "3") (pinfunction "C_3") (pintype "passive"))
      (node (ref "ULN1") (pin "14") (pinfunction "14_14") (pintype "bidirectional"))
    )
    (net (code "46") (name "Net-(OK2-A)") (class "Default")
      (node (ref "OK2") (pin "2") (pinfunction "A_2") (pintype "passive"))
      (node (ref "R6") (pin "2") (pinfunction "2_2") (pintype "passive"))
    )
    (net (code "47") (name "Net-(OK2-C)") (class "Default")
      (node (ref "OK2") (pin "3") (pinfunction "C_3") (pintype "passive"))
      (node (ref "ULN1") (pin "13") (pinfunction "13_13") (pintype "bidirectional"))
    )
    (net (code "48") (name "Net-(OK3A-A)") (class "Default")
      (node (ref "OK3") (pin "1") (pinfunction "A_1") (pintype "passive"))
      (node (ref "R7") (pin "2") (pinfunction "2_2") (pintype "passive"))
    )
    (net (code "49") (name "Net-(OK3A-C)") (class "Default")
      (node (ref "OK3") (pin "2") (pinfunction "C_2") (pintype "passive"))
      (node (ref "ULN1") (pin "12") (pinfunction "12_12") (pintype "bidirectional"))
    )
    (net (code "50") (name "Net-(OK3B-A)") (class "Default")
      (node (ref "OK3") (pin "3") (pinfunction "A_3") (pintype "passive"))
      (node (ref "R8") (pin "2") (pinfunction "2_2") (pintype "passive"))
    )
    (net (code "51") (name "Net-(OK3B-C)") (class "Default")
      (node (ref "OK3") (pin "4") (pinfunction "C_4") (pintype "passive"))
      (node (ref "ULN1") (pin "11") (pinfunction "11_11") (pintype "bidirectional"))
    )
    (net (code "52") (name "Net-(PCB1-PadD2)") (class "Default")
      (node (ref "PCB1") (pin "D2") (pinfunction "D2_D2") (pintype "bidirectional"))
      (node (ref "ULN1") (pin "1") (pinfunction "1_1") (pintype "bidirectional"))
    )
    (net (code "53") (name "Net-(PCB1-PadD3)") (class "Default")
      (node (ref "PCB1") (pin "D3") (pinfunction "D3_D3") (pintype "bidirectional"))
      (node (ref "ULN1") (pin "2") (pinfunction "2_2") (pintype "bidirectional"))
    )
    (net (code "54") (name "Net-(PCB1-PadD4)") (class "Default")
      (node (ref "PCB1") (pin "D4") (pinfunction "D4_D4") (pintype "bidirectional"))
      (node (ref "ULN1") (pin "3") (pinfunction "3_3") (pintype "bidirectional"))
    )
    (net (code "55") (name "Net-(PCB1-PadD5)") (class "Default")
      (node (ref "PCB1") (pin "D5") (pinfunction "D5_D5") (pintype "bidirectional"))
      (node (ref "ULN1") (pin "4") (pinfunction "4_4") (pintype "bidirectional"))
    )
    (net (code "56") (name "Net-(PCB1-PadD6)") (class "Default")
      (node (ref "PCB1") (pin "D6") (pinfunction "D6_D6") (pintype "bidirectional"))
      (node (ref "ULN1") (pin "5") (pinfunction "5_5") (pintype "bidirectional"))
    )
    (net (code "57") (name "Net-(PCB1-PadD7)") (class "Default")
      (node (ref "PCB1") (pin "D7") (pinfunction "D7_D7") (pintype "bidirectional"))
      (node (ref "ULN1") (pin "6") (pinfunction "6_6") (pintype "bidirectional"))
    )
    (net (code "58") (name "Net-(PCB1-PadD8)") (class "Default")
      (node (ref "PCB1") (pin "D8") (pinfunction "D8_D8") (pintype "bidirectional"))
      (node (ref "ULN1") (pin "7") (pinfunction "7_7") (pintype "bidirectional"))
    )
    (net (code "59") (name "Net-(PCB1-PadD9)") (class "Default")
      (node (ref "PCB1") (pin "D9") (pinfunction "D9_D9") (pintype "bidirectional"))
      (node (ref "ULN1") (pin "8") (pinfunction "8_8") (pintype "bidirectional"))
    )
    (net (code "60") (name "Net-(X1A-KL)") (class "Default")
      (node (ref "U$2") (pin "A") (pinfunction "A_A") (pintype "passive"))
      (node (ref "U$4") (pin "C") (pinfunction "C_C") (pintype "passive"))
      (node (ref "X1") (pin "1") (pinfunction "KL_1") (pintype "passive"))
    )
    (net (code "61") (name "Net-(X1B-KL)") (class "Default")
      (node (ref "U$1") (pin "A") (pinfunction "A_A") (pintype "passive"))
      (node (ref "U$3") (pin "C") (pinfunction "C_C") (pintype "passive"))
      (node (ref "X1") (pin "2") (pinfunction "KL_2") (pintype "passive"))
    )
    (net (code "62") (name "Net-(X2A-KL)") (class "Default")
      (node (ref "U$6") (pin "A") (pinfunction "A_A") (pintype "passive"))
      (node (ref "U$8") (pin "C") (pinfunction "C_C") (pintype "passive"))
      (node (ref "X2") (pin "1") (pinfunction "KL_1") (pintype "passive"))
    )
    (net (code "63") (name "Net-(X2B-KL)") (class "Default")
      (node (ref "U$5") (pin "A") (pinfunction "A_A") (pintype "passive"))
      (node (ref "U$7") (pin "C") (pinfunction "C_C") (pintype "passive"))
      (node (ref "X2") (pin "2") (pinfunction "KL_2") (pintype "passive"))
    )
    (net (code "64") (name "Net-(X15B-KL)") (class "Default")
      (node (ref "X15") (pin "2") (pinfunction "KL_2") (pintype "passive"))
      (node (ref "X16") (pin "2") (pinfunction "KL_2") (pintype "passive"))
      (node (ref "X17") (pin "2") (pinfunction "KL_2") (pintype "passive"))
      (node (ref "X18") (pin "2") (pinfunction "KL_2") (pintype "passive"))
      (node (ref "X19") (pin "2") (pinfunction "KL_2") (pintype "passive"))
      (node (ref "X20") (pin "2") (pinfunction "KL_2") (pintype "passive"))
      (node (ref "X21") (pin "2") (pinfunction "KL_2") (pintype "passive"))
    )
    (net (code "65") (name "OUT1") (class "Default")
      (node (ref "K1") (pin "1") (pinfunction "1_1") (pintype "passive"))
      (node (ref "K2") (pin "1") (pinfunction "1_1") (pintype "passive"))
      (node (ref "ULN2") (pin "13") (pinfunction "13_13") (pintype "bidirectional"))
    )
    (net (code "66") (name "OUT2") (class "Default")
      (node (ref "K10") (pin "1") (pinfunction "1_1") (pintype "passive"))
      (node (ref "K9") (pin "1") (pinfunction "1_1") (pintype "passive"))
      (node (ref "ULN2") (pin "12") (pinfunction "12_12") (pintype "bidirectional"))
    )
    (net (code "67") (name "OUT3") (class "Default")
      (node (ref "K11") (pin "1") (pinfunction "1_1") (pintype "passive"))
      (node (ref "ULN2") (pin "11") (pinfunction "11_11") (pintype "bidirectional"))
    )
    (net (code "68") (name "R+1") (class "Default")
      (node (ref "K3") (pin "9") (pinfunction "S_9") (pintype "passive"))
      (node (ref "X3") (pin "1") (pinfunction "KL_1") (pintype "passive"))
    )
    (net (code "69") (name "R+2") (class "Default")
      (node (ref "K4") (pin "9") (pinfunction "S_9") (pintype "passive"))
      (node (ref "X5") (pin "1") (pinfunction "KL_1") (pintype "passive"))
    )
    (net (code "70") (name "R+3") (class "Default")
      (node (ref "K7") (pin "9") (pinfunction "S_9") (pintype "passive"))
      (node (ref "X11") (pin "1") (pinfunction "KL_1") (pintype "passive"))
    )
    (net (code "71") (name "R+IN") (class "Default")
      (node (ref "K3") (pin "11") (pinfunction "O_11") (pintype "passive"))
      (node (ref "K4") (pin "11") (pinfunction "O_11") (pintype "passive"))
      (node (ref "K7") (pin "11") (pinfunction "O_11") (pintype "passive"))
      (node (ref "KBPR") (pin "9") (pinfunction "S_9") (pintype "passive"))
      (node (ref "U1") (pin "3") (pinfunction "+IN_3") (pintype "bidirectional"))
      (node (ref "X13") (pin "3") (pinfunction "KL_3") (pintype "passive"))
    )
    (net (code "72") (name "R-1") (class "Default")
      (node (ref "K3") (pin "8") (pinfunction "S_8") (pintype "passive"))
      (node (ref "X3") (pin "3") (pinfunction "KL_3") (pintype "passive"))
    )
    (net (code "73") (name "R-2") (class "Default")
      (node (ref "K4") (pin "8") (pinfunction "S_8") (pintype "passive"))
      (node (ref "X5") (pin "3") (pinfunction "KL_3") (pintype "passive"))
    )
    (net (code "74") (name "R-3") (class "Default")
      (node (ref "K7") (pin "8") (pinfunction "S_8") (pintype "passive"))
      (node (ref "X11") (pin "3") (pinfunction "KL_3") (pintype "passive"))
    )
    (net (code "75") (name "R-IN") (class "Default")
      (node (ref "K3") (pin "6") (pinfunction "O_6") (pintype "passive"))
      (node (ref "K4") (pin "6") (pinfunction "O_6") (pintype "passive"))
      (node (ref "K7") (pin "6") (pinfunction "O_6") (pintype "passive"))
      (node (ref "KBPR") (pin "8") (pinfunction "S_8") (pintype "passive"))
      (node (ref "U2") (pin "3") (pinfunction "+IN_3") (pintype "bidirectional"))
      (node (ref "X13") (pin "1") (pinfunction "KL_1") (pintype "passive"))
    )
    (net (code "76") (name "RPGA+") (class "Default")
      (node (ref "IC3") (pin "14") (pinfunction "AOUTL_14") (pintype "output"))
      (node (ref "KBPR") (pin "13") (pinfunction "P_13") (pintype "passive"))
      (node (ref "X7") (pin "1") (pinfunction "KL_1") (pintype "passive"))
    )
    (net (code "77") (name "RPGA-") (class "Default")
      (node (ref "IC3") (pin "11") (pinfunction "AOUTR_11") (pintype "output"))
      (node (ref "KBPR") (pin "4") (pinfunction "P_4") (pintype "passive"))
      (node (ref "X7") (pin "3") (pinfunction "KL_3") (pintype "passive"))
    )
    (net (code "78") (name "SCLK") (class "Default")
      (node (ref "IC3") (pin "6") (pinfunction "SCLK_6") (pintype "input"))
      (node (ref "IC4") (pin "6") (pinfunction "SCLK_6") (pintype "input"))
      (node (ref "OK2") (pin "6") (pinfunction "VO_6") (pintype "passive"))
      (node (ref "R10") (pin "2") (pinfunction "2_2") (pintype "passive"))
    )
    (net (code "79") (name "SDATA") (class "Default")
      (node (ref "IC3") (pin "3") (pinfunction "SDATAI_3") (pintype "input"))
      (node (ref "IC4") (pin "3") (pinfunction "SDATAI_3") (pintype "input"))
      (node (ref "OK1") (pin "6") (pinfunction "VO_6") (pintype "passive"))
      (node (ref "R9") (pin "2") (pinfunction "2_2") (pintype "passive"))
    )
    (net (code "80") (name "SEL1") (class "Default")
      (node (ref "K3") (pin "1") (pinfunction "1_1") (pintype "passive"))
      (node (ref "K5") (pin "1") (pinfunction "1_1") (pintype "passive"))
      (node (ref "ULN1") (pin "17") (pinfunction "17_17") (pintype "bidirectional"))
    )
    (net (code "81") (name "SEL2") (class "Default")
      (node (ref "K4") (pin "1") (pinfunction "1_1") (pintype "passive"))
      (node (ref "K6") (pin "1") (pinfunction "1_1") (pintype "passive"))
      (node (ref "ULN1") (pin "16") (pinfunction "16_16") (pintype "bidirectional"))
    )
    (net (code "82") (name "SEL3") (class "Default")
      (node (ref "K7") (pin "1") (pinfunction "1_1") (pintype "passive"))
      (node (ref "K8") (pin "1") (pinfunction "1_1") (pintype "passive"))
      (node (ref "ULN1") (pin "15") (pinfunction "15_15") (pintype "bidirectional"))
    )
    (net (code "83") (name "unconnected-(IC3-SDATAO-Pad7)") (class "Default")
      (node (ref "IC3") (pin "7") (pinfunction "SDATAO_7") (pintype "output"))
    )
    (net (code "84") (name "unconnected-(IC4-SDATAO-Pad7)") (class "Default")
      (node (ref "IC4") (pin "7") (pinfunction "SDATAO_7") (pintype "output"))
    )
    (net (code "85") (name "unconnected-(K1A-P-Pad4)") (class "Default")
      (node (ref "K1") (pin "4") (pinfunction "P_4") (pintype "passive"))
    )
    (net (code "86") (name "unconnected-(K1B-P-Pad13)") (class "Default")
      (node (ref "K1") (pin "13") (pinfunction "P_13") (pintype "passive"))
    )
    (net (code "87") (name "unconnected-(K2A-P-Pad4)") (class "Default")
      (node (ref "K2") (pin "4") (pinfunction "P_4") (pintype "passive"))
    )
    (net (code "88") (name "unconnected-(K2B-P-Pad13)") (class "Default")
      (node (ref "K2") (pin "13") (pinfunction "P_13") (pintype "passive"))
    )
    (net (code "89") (name "unconnected-(K3A-P-Pad4)") (class "Default")
      (node (ref "K3") (pin "4") (pinfunction "P_4") (pintype "passive"))
    )
    (net (code "90") (name "unconnected-(K3B-P-Pad13)") (class "Default")
      (node (ref "K3") (pin "13") (pinfunction "P_13") (pintype "passive"))
    )
    (net (code "91") (name "unconnected-(K4A-P-Pad4)") (class "Default")
      (node (ref "K4") (pin "4") (pinfunction "P_4") (pintype "passive"))
    )
    (net (code "92") (name "unconnected-(K4B-P-Pad13)") (class "Default")
      (node (ref "K4") (pin "13") (pinfunction "P_13") (pintype "passive"))
    )
    (net (code "93") (name "unconnected-(K5A-P-Pad4)") (class "Default")
      (node (ref "K5") (pin "4") (pinfunction "P_4") (pintype "passive"))
    )
    (net (code "94") (name "unconnected-(K5B-P-Pad13)") (class "Default")
      (node (ref "K5") (pin "13") (pinfunction "P_13") (pintype "passive"))
    )
    (net (code "95") (name "unconnected-(K6A-P-Pad4)") (class "Default")
      (node (ref "K6") (pin "4") (pinfunction "P_4") (pintype "passive"))
    )
    (net (code "96") (name "unconnected-(K6B-P-Pad13)") (class "Default")
      (node (ref "K6") (pin "13") (pinfunction "P_13") (pintype "passive"))
    )
    (net (code "97") (name "unconnected-(K7A-P-Pad4)") (class "Default")
      (node (ref "K7") (pin "4") (pinfunction "P_4") (pintype "passive"))
    )
    (net (code "98") (name "unconnected-(K7B-P-Pad13)") (class "Default")
      (node (ref "K7") (pin "13") (pinfunction "P_13") (pintype "passive"))
    )
    (net (code "99") (name "unconnected-(K8A-P-Pad4)") (class "Default")
      (node (ref "K8") (pin "4") (pinfunction "P_4") (pintype "passive"))
    )
    (net (code "100") (name "unconnected-(K8B-P-Pad13)") (class "Default")
      (node (ref "K8") (pin "13") (pinfunction "P_13") (pintype "passive"))
    )
    (net (code "101") (name "unconnected-(K9A-P-Pad4)") (class "Default")
      (node (ref "K9") (pin "4") (pinfunction "P_4") (pintype "passive"))
    )
    (net (code "102") (name "unconnected-(K9B-P-Pad13)") (class "Default")
      (node (ref "K9") (pin "13") (pinfunction "P_13") (pintype "passive"))
    )
    (net (code "103") (name "unconnected-(K10A-P-Pad4)") (class "Default")
      (node (ref "K10") (pin "4") (pinfunction "P_4") (pintype "passive"))
    )
    (net (code "104") (name "unconnected-(K10B-P-Pad13)") (class "Default")
      (node (ref "K10") (pin "13") (pinfunction "P_13") (pintype "passive"))
    )
    (net (code "105") (name "unconnected-(K11A-P-Pad4)") (class "Default")
      (node (ref "K11") (pin "4") (pinfunction "P_4") (pintype "passive"))
    )
    (net (code "106") (name "unconnected-(K11B-P-Pad13)") (class "Default")
      (node (ref "K11") (pin "13") (pinfunction "P_13") (pintype "passive"))
    )
    (net (code "107") (name "unconnected-(KBPLA-O-Pad6)") (class "Default")
      (node (ref "KBPL") (pin "6") (pinfunction "O_6") (pintype "passive"))
    )
    (net (code "108") (name "unconnected-(KBPLB-O-Pad11)") (class "Default")
      (node (ref "KBPL") (pin "11") (pinfunction "O_11") (pintype "passive"))
    )
    (net (code "109") (name "unconnected-(KBPRA-O-Pad6)") (class "Default")
      (node (ref "KBPR") (pin "6") (pinfunction "O_6") (pintype "passive"))
    )
    (net (code "110") (name "unconnected-(KBPRB-O-Pad11)") (class "Default")
      (node (ref "KBPR") (pin "11") (pinfunction "O_11") (pintype "passive"))
    )
    (net (code "111") (name "unconnected-(OK3A-EMIT-Pad7)") (class "Default")
      (node (ref "OK3") (pin "7") (pinfunction "EMIT_7") (pintype "passive"))
    )
    (net (code "112") (name "unconnected-(OK3B-EMIT-Pad5)") (class "Default")
      (node (ref "OK3") (pin "5") (pinfunction "EMIT_5") (pintype "passive"))
    )
    (net (code "113") (name "unconnected-(PCB1-Pad3V3)") (class "Default")
      (node (ref "PCB1") (pin "3V3") (pinfunction "3V3_3V3") (pintype "bidirectional"))
    )
    (net (code "114") (name "unconnected-(PCB1-Pad5V)") (class "Default")
      (node (ref "PCB1") (pin "5V") (pinfunction "5V_5V") (pintype "bidirectional"))
    )
    (net (code "115") (name "unconnected-(PCB1-PadA0)") (class "Default")
      (node (ref "PCB1") (pin "A0") (pinfunction "A0_A0") (pintype "bidirectional"))
    )
    (net (code "116") (name "unconnected-(PCB1-PadA1)") (class "Default")
      (node (ref "PCB1") (pin "A1") (pinfunction "A1_A1") (pintype "bidirectional"))
    )
    (net (code "117") (name "unconnected-(PCB1-PadA2)") (class "Default")
      (node (ref "PCB1") (pin "A2") (pinfunction "A2_A2") (pintype "bidirectional"))
    )
    (net (code "118") (name "unconnected-(PCB1-PadA3)") (class "Default")
      (node (ref "PCB1") (pin "A3") (pinfunction "A3_A3") (pintype "bidirectional"))
    )
    (net (code "119") (name "unconnected-(PCB1-PadA4)") (class "Default")
      (node (ref "PCB1") (pin "A4") (pinfunction "A4_A4") (pintype "bidirectional"))
    )
    (net (code "120") (name "unconnected-(PCB1-PadA5)") (class "Default")
      (node (ref "PCB1") (pin "A5") (pinfunction "A5_A5") (pintype "bidirectional"))
    )
    (net (code "121") (name "unconnected-(PCB1-PadA6)") (class "Default")
      (node (ref "PCB1") (pin "A6") (pinfunction "A6_A6") (pintype "bidirectional"))
    )
    (net (code "122") (name "unconnected-(PCB1-PadA7)") (class "Default")
      (node (ref "PCB1") (pin "A7") (pinfunction "A7_A7") (pintype "bidirectional"))
    )
    (net (code "123") (name "unconnected-(PCB1-PadD13)") (class "Default")
      (node (ref "PCB1") (pin "D13") (pinfunction "D13_D13") (pintype "bidirectional"))
    )
    (net (code "124") (name "unconnected-(PCB1-PadGND)") (class "Default")
      (node (ref "PCB1") (pin "GND") (pinfunction "GND_GND") (pintype "bidirectional"))
    )
    (net (code "125") (name "unconnected-(PCB1-PadREF)") (class "Default")
      (node (ref "PCB1") (pin "REF") (pinfunction "REF_REF") (pintype "bidirectional"))
    )
    (net (code "126") (name "unconnected-(PCB1-PadRST)") (class "Default")
      (node (ref "PCB1") (pin "RST") (pinfunction "RST_RST") (pintype "bidirectional"))
    )
    (net (code "127") (name "unconnected-(PCB1-PadRST.)") (class "Default")
      (node (ref "PCB1") (pin "RST.") (pinfunction "RST._RST.") (pintype "bidirectional"))
    )
    (net (code "128") (name "unconnected-(PCB1-PadTX1)") (class "Default")
      (node (ref "PCB1") (pin "TX1") (pinfunction "TX1_TX1") (pintype "bidirectional"))
    )
    (net (code "129") (name "unconnected-(PCB1-RX0-PadRX1)") (class "Default")
      (node (ref "PCB1") (pin "RX1") (pinfunction "RX0_RX1") (pintype "bidirectional"))
    )
    (net (code "130") (name "unconnected-(ULN2-Pad1)") (class "Default")
      (node (ref "ULN2") (pin "1") (pinfunction "1_1") (pintype "bidirectional"))
    )
    (net (code "131") (name "unconnected-(ULN2-Pad2)") (class "Default")
      (node (ref "ULN2") (pin "2") (pinfunction "2_2") (pintype "bidirectional"))
    )
    (net (code "132") (name "unconnected-(ULN2-Pad3)") (class "Default")
      (node (ref "ULN2") (pin "3") (pinfunction "3_3") (pintype "bidirectional"))
    )
    (net (code "133") (name "unconnected-(ULN2-Pad4)") (class "Default")
      (node (ref "ULN2") (pin "4") (pinfunction "4_4") (pintype "bidirectional"))
    )
    (net (code "134") (name "unconnected-(ULN2-Pad5)") (class "Default")
      (node (ref "ULN2") (pin "5") (pinfunction "5_5") (pintype "bidirectional"))
    )
    (net (code "135") (name "unconnected-(ULN2-Pad14)") (class "Default")
      (node (ref "ULN2") (pin "14") (pinfunction "14_14") (pintype "bidirectional"))
    )
    (net (code "136") (name "unconnected-(ULN2-Pad15)") (class "Default")
      (node (ref "ULN2") (pin "15") (pinfunction "15_15") (pintype "bidirectional"))
    )
    (net (code "137") (name "unconnected-(ULN2-Pad16)") (class "Default")
      (node (ref "ULN2") (pin "16") (pinfunction "16_16") (pintype "bidirectional"))
    )
    (net (code "138") (name "unconnected-(ULN2-Pad17)") (class "Default")
      (node (ref "ULN2") (pin "17") (pinfunction "17_17") (pintype "bidirectional"))
    )
    (net (code "139") (name "unconnected-(ULN2-Pad18)") (class "Default")
      (node (ref "ULN2") (pin "18") (pinfunction "18_18") (pintype "bidirectional"))
    )
  )
)
